# LED-PCB_Connector.net
KiCad netlist of a schematic drawn in Altium Designer
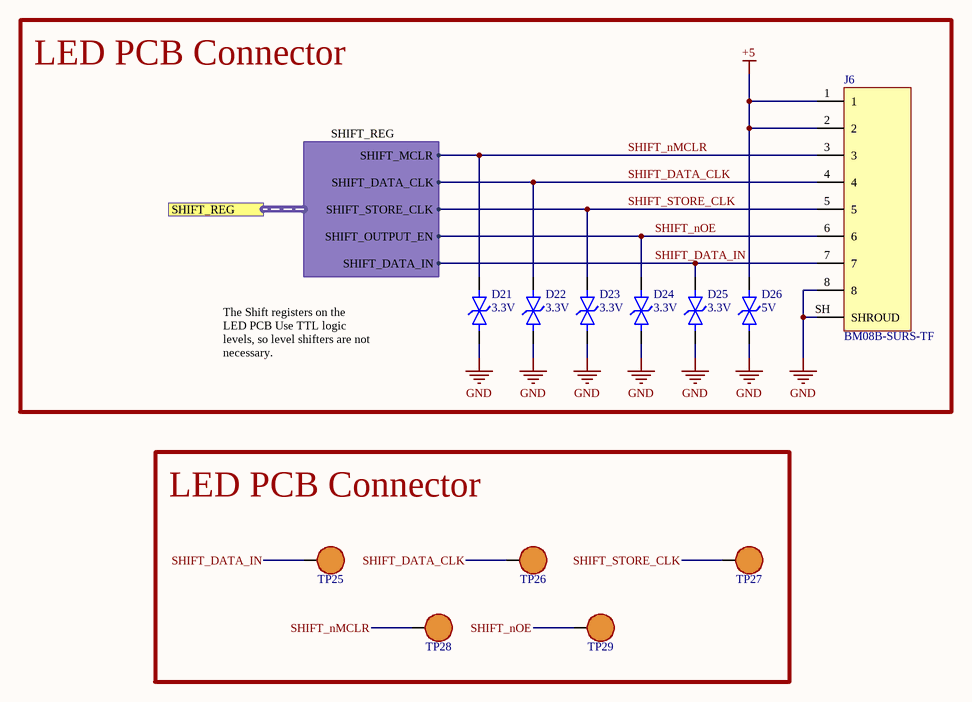
[diagram p0: LED-PCB_Connector.SchDoc]

(export (version "E")
  (design (tool "Eeschema 10.0.6"))
  (components
    (comp (ref "D21")
      (value "DESD3V3E1BL-7B")
      (footprint "Beethoven-clock:0402-TVS")
      (description "TVS DIODE 3.3VWM 7VC DFN1006-2")
      (fields (field (name "MFR") "Diodes Incorporated") (field (name "VRS") "3.3V"))
      (libsource (lib "Beethoven-clock") (part "TVS Diode 3.3V Bi"))
    )
    (comp (ref "D22")
      (value "DESD3V3E1BL-7B")
      (footprint "Beethoven-clock:0402-TVS")
      (description "TVS DIODE 3.3VWM 7VC DFN1006-2")
      (fields (field (name "MFR") "Diodes Incorporated") (field (name "VRS") "3.3V"))
      (libsource (lib "Beethoven-clock") (part "TVS Diode 3.3V Bi"))
    )
    (comp (ref "D23")
      (value "DESD3V3E1BL-7B")
      (footprint "Beethoven-clock:0402-TVS")
      (description "TVS DIODE 3.3VWM 7VC DFN1006-2")
      (fields (field (name "MFR") "Diodes Incorporated") (field (name "VRS") "3.3V"))
      (libsource (lib "Beethoven-clock") (part "TVS Diode 3.3V Bi"))
    )
    (comp (ref "D24")
      (value "DESD3V3E1BL-7B")
      (footprint "Beethoven-clock:0402-TVS")
      (description "TVS DIODE 3.3VWM 7VC DFN1006-2")
      (fields (field (name "MFR") "Diodes Incorporated") (field (name "VRS") "3.3V"))
      (libsource (lib "Beethoven-clock") (part "TVS Diode 3.3V Bi"))
    )
    (comp (ref "D25")
      (value "DESD3V3E1BL-7B")
      (footprint "Beethoven-clock:0402-TVS")
      (description "TVS DIODE 3.3VWM 7VC DFN1006-2")
      (fields (field (name "MFR") "Diodes Incorporated") (field (name "VRS") "3.3V"))
      (libsource (lib "Beethoven-clock") (part "TVS Diode 3.3V Bi"))
    )
    (comp (ref "D26")
      (value "DESD5V0U1BL-7B")
      (footprint "Beethoven-clock:0402-TVS")
      (description "TVS DIODE 5VWM 7.2VC DFN1006-2")
      (fields (field (name "MFR") "Diodes Incorporated") (field (name "VRS") "5V"))
      (libsource (lib "Beethoven-clock") (part "TVS Diode 5V Bi"))
    )
    (comp (ref "J6")
      (value "BM08B-SURS-TF")
      (footprint "Beethoven-clock:JST_BM08B-SURS-TF(LF)(SN)")
      (description "CONN HEADER SMD 8POS 0.8MM")
      (fields (field (name "MFR") "JST"))
      (libsource (lib "Beethoven-clock") (part "CONN 8POS 0.8MM PITCH"))
    )
    (comp (ref "TP25")
      (value "RCWCTE")
      (footprint "Beethoven-clock:RCWCTE")
      (description "Test Point, Surface Mount")
      (fields (field (name "MFR") "KOA Speer Electronics, Inc."))
      (libsource (lib "Beethoven-clock") (part "TEST POINT"))
    )
    (comp (ref "TP26")
      (value "RCWCTE")
      (footprint "Beethoven-clock:RCWCTE")
      (description "Test Point, Surface Mount")
      (fields (field (name "MFR") "KOA Speer Electronics, Inc."))
      (libsource (lib "Beethoven-clock") (part "TEST POINT"))
    )
    (comp (ref "TP27")
      (value "RCWCTE")
      (footprint "Beethoven-clock:RCWCTE")
      (description "Test Point, Surface Mount")
      (fields (field (name "MFR") "KOA Speer Electronics, Inc."))
      (libsource (lib "Beethoven-clock") (part "TEST POINT"))
    )
    (comp (ref "TP28")
      (value "RCWCTE")
      (footprint "Beethoven-clock:RCWCTE")
      (description "Test Point, Surface Mount")
      (fields (field (name "MFR") "KOA Speer Electronics, Inc."))
      (libsource (lib "Beethoven-clock") (part "TEST POINT"))
    )
    (comp (ref "TP29")
      (value "RCWCTE")
      (footprint "Beethoven-clock:RCWCTE")
      (description "Test Point, Surface Mount")
      (fields (field (name "MFR") "KOA Speer Electronics, Inc."))
      (libsource (lib "Beethoven-clock") (part "TEST POINT"))
    )
  )
  (nets
    (net (code "2") (name "+5") (class "Default")
      (node (ref "D26") (pin "1") (pinfunction "1_1") (pintype "passive"))
      (node (ref "J6") (pin "1") (pinfunction "1_1") (pintype "passive"))
      (node (ref "J6") (pin "2") (pinfunction "2_2") (pintype "passive"))
    )
    (net (code "3") (name "/SHIFT_DATA_CLK") (class "Default")
      (node (ref "D22") (pin "1") (pinfunction "1_1") (pintype "passive"))
      (node (ref "J6") (pin "4") (pinfunction "4_4") (pintype "passive"))
      (node (ref "TP26") (pin "1") (pinfunction "0_1") (pintype "passive"))
    )
    (net (code "4") (name "/SHIFT_DATA_IN") (class "Default")
      (node (ref "D25") (pin "1") (pinfunction "1_1") (pintype "passive"))
      (node (ref "J6") (pin "7") (pinfunction "7_7") (pintype "passive"))
      (node (ref "TP25") (pin "1") (pinfunction "0_1") (pintype "passive"))
    )
    (net (code "5") (name "/SHIFT_STORE_CLK") (class "Default")
      (node (ref "D23") (pin "1") (pinfunction "1_1") (pintype "passive"))
      (node (ref "J6") (pin "5") (pinfunction "5_5") (pintype "passive"))
      (node (ref "TP27") (pin "1") (pinfunction "0_1") (pintype "passive"))
    )
    (net (code "6") (name "/SHIFT_nMCLR") (class "Default")
      (node (ref "D21") (pin "1") (pinfunction "1_1") (pintype "passive"))
      (node (ref "J6") (pin "3") (pinfunction "3_3") (pintype "passive"))
      (node (ref "TP28") (pin "1") (pinfunction "0_1") (pintype "passive"))
    )
    (net (code "7") (name "/SHIFT_nOE") (class "Default")
      (node (ref "D24") (pin "1") (pinfunction "1_1") (pintype "passive"))
      (node (ref "J6") (pin "6") (pinfunction "6_6") (pintype "passive"))
      (node (ref "TP29") (pin "1") (pinfunction "0_1") (pintype "passive"))
    )
    (net (code "9") (name "GND") (class "Default")
      (node (ref "D21") (pin "2") (pinfunction "2_2") (pintype "passive"))
      (node (ref "D22") (pin "2") (pinfunction "2_2") (pintype "passive"))
      (node (ref "D23") (pin "2") (pinfunction "2_2") (pintype "passive"))
      (node (ref "D24") (pin "2") (pinfunction "2_2") (pintype "passive"))
      (node (ref "D25") (pin "2") (pinfunction "2_2") (pintype "passive"))
      (node (ref "D26") (pin "2") (pinfunction "2_2") (pintype "passive"))
      (node (ref "J6") (pin "8") (pinfunction "8_8") (pintype "passive"))
      (node (ref "J6") (pin "SH") (pinfunction "SHROUD_SH") (pintype "passive"))
    )
  )
)
